# HHKBLite2BT.net
KiCad netlist of a schematic drawn in EAGLE
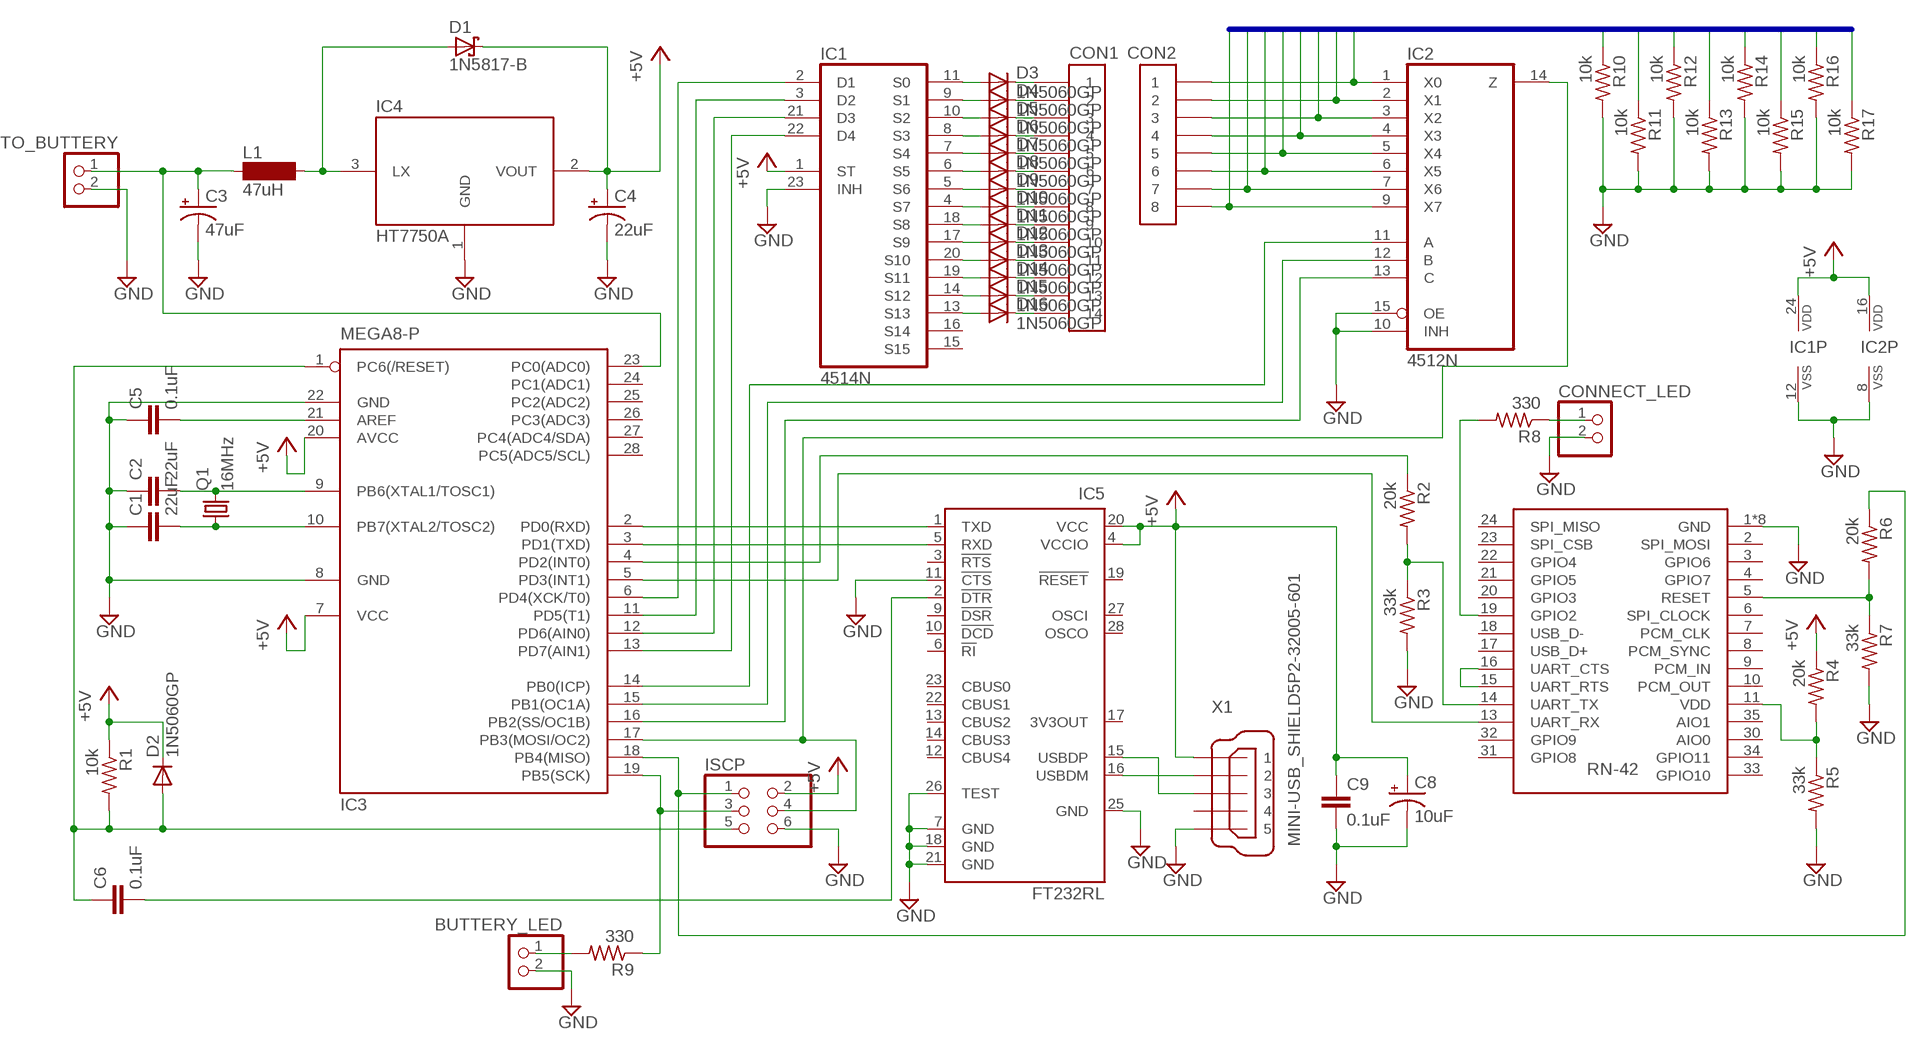
[diagram p0: schematic, sheet 1]

(export (version "E")
  (design (tool "Eeschema 10.0.6"))
  (components
    (comp (ref "BUTTERY_LED")
      (value "PINHD-1X2")
      (footprint "eagle-import:1X02")
      (libsource (lib "eagle-import") (part "PINHD-1X2"))
    )
    (comp (ref "C1")
      (value "22uF")
      (footprint "eagle-import:C5B2.5")
      (libsource (lib "eagle-import") (part "C5/2.5"))
    )
    (comp (ref "C2")
      (value "22uF")
      (footprint "eagle-import:C5B2.5")
      (libsource (lib "eagle-import") (part "C5/2.5"))
    )
    (comp (ref "C3")
      (value "47uF")
      (footprint "eagle-import:E5-10,5")
      (libsource (lib "eagle-import") (part "CPOL-USE5-10.5"))
    )
    (comp (ref "C4")
      (value "22uF")
      (footprint "eagle-import:E5-10,5")
      (libsource (lib "eagle-import") (part "CPOL-USE5-10.5"))
    )
    (comp (ref "C5")
      (value "0.1uF")
      (footprint "eagle-import:C5B2.5")
      (libsource (lib "eagle-import") (part "C5/2.5"))
    )
    (comp (ref "C6")
      (value "0.1uF")
      (footprint "eagle-import:C5B2.5")
      (libsource (lib "eagle-import") (part "C5/2.5"))
    )
    (comp (ref "C8")
      (value "10uF")
      (footprint "eagle-import:E5-10,5")
      (libsource (lib "eagle-import") (part "CPOL-USE5-10.5"))
    )
    (comp (ref "C9")
      (value "0.1uF")
      (footprint "eagle-import:C5B2.5")
      (libsource (lib "eagle-import") (part "C5/2.5"))
    )
    (comp (ref "CON1")
      (value "45045-1445")
      (footprint "eagle-import:52045-1445")
      (libsource (lib "eagle-import") (part "45045-1445"))
    )
    (comp (ref "CON2")
      (value "45045-0845")
      (footprint "eagle-import:52045-0845")
      (libsource (lib "eagle-import") (part "45045-0845"))
    )
    (comp (ref "CONNECT_LED")
      (value "PINHD-1X2")
      (footprint "eagle-import:1X02")
      (libsource (lib "eagle-import") (part "PINHD-1X2"))
    )
    (comp (ref "D1")
      (value "1N5817-B")
      (footprint "eagle-import:DO41-7.6")
      (libsource (lib "eagle-import") (part "1N5817-B"))
    )
    (comp (ref "D2")
      (value "1N5060GP")
      (footprint "eagle-import:DO15-12")
      (libsource (lib "eagle-import") (part "1N5060GP"))
    )
    (comp (ref "D3")
      (value "1N5060GP")
      (footprint "eagle-import:DO15-12")
      (libsource (lib "eagle-import") (part "1N5060GP"))
    )
    (comp (ref "D4")
      (value "1N5060GP")
      (footprint "eagle-import:DO15-12")
      (libsource (lib "eagle-import") (part "1N5060GP"))
    )
    (comp (ref "D5")
      (value "1N5060GP")
      (footprint "eagle-import:DO15-12")
      (libsource (lib "eagle-import") (part "1N5060GP"))
    )
    (comp (ref "D6")
      (value "1N5060GP")
      (footprint "eagle-import:DO15-12")
      (libsource (lib "eagle-import") (part "1N5060GP"))
    )
    (comp (ref "D7")
      (value "1N5060GP")
      (footprint "eagle-import:DO15-12")
      (libsource (lib "eagle-import") (part "1N5060GP"))
    )
    (comp (ref "D8")
      (value "1N5060GP")
      (footprint "eagle-import:DO15-12")
      (libsource (lib "eagle-import") (part "1N5060GP"))
    )
    (comp (ref "D9")
      (value "1N5060GP")
      (footprint "eagle-import:DO15-12")
      (libsource (lib "eagle-import") (part "1N5060GP"))
    )
    (comp (ref "D10")
      (value "1N5060GP")
      (footprint "eagle-import:DO15-12")
      (libsource (lib "eagle-import") (part "1N5060GP"))
    )
    (comp (ref "D11")
      (value "1N5060GP")
      (footprint "eagle-import:DO15-12")
      (libsource (lib "eagle-import") (part "1N5060GP"))
    )
    (comp (ref "D12")
      (value "1N5060GP")
      (footprint "eagle-import:DO15-12")
      (libsource (lib "eagle-import") (part "1N5060GP"))
    )
    (comp (ref "D13")
      (value "1N5060GP")
      (footprint "eagle-import:DO15-12")
      (libsource (lib "eagle-import") (part "1N5060GP"))
    )
    (comp (ref "D14")
      (value "1N5060GP")
      (footprint "eagle-import:DO15-12")
      (libsource (lib "eagle-import") (part "1N5060GP"))
    )
    (comp (ref "D15")
      (value "1N5060GP")
      (footprint "eagle-import:DO15-12")
      (libsource (lib "eagle-import") (part "1N5060GP"))
    )
    (comp (ref "D16")
      (value "1N5060GP")
      (footprint "eagle-import:DO15-12")
      (libsource (lib "eagle-import") (part "1N5060GP"))
    )
    (comp (ref "IC1")
      (value "4514N")
      (footprint "eagle-import:DIL24-6")
      (libsource (lib "eagle-import") (part "4514N"))
    )
    (comp (ref "IC2")
      (value "4512N")
      (footprint "eagle-import:DIL16")
      (libsource (lib "eagle-import") (part "4512N"))
    )
    (comp (ref "IC3")
      (value "MEGA8-P")
      (footprint "eagle-import:DIL28-3")
      (libsource (lib "eagle-import") (part "MEGA8-P"))
    )
    (comp (ref "IC4")
      (value "HT7750A")
      (footprint "eagle-import:TO-92")
      (libsource (lib "eagle-import") (part "HT7750A"))
    )
    (comp (ref "IC5")
      (value "FT232RL")
      (footprint "eagle-import:SSOP28")
      (libsource (lib "eagle-import") (part "FT232RL"))
    )
    (comp (ref "ISCP")
      (value "PINHD-2X3")
      (footprint "eagle-import:2X03")
      (libsource (lib "eagle-import") (part "PINHD-2X3"))
    )
    (comp (ref "L1")
      (value "47uH")
      (footprint "eagle-import:BS11")
      (libsource (lib "eagle-import") (part "BS11"))
    )
    (comp (ref "Q1")
      (value "16MHz")
      (footprint "eagle-import:HC49_S")
      (libsource (lib "eagle-import") (part "CRYSTALHC49S"))
    )
    (comp (ref "R1")
      (value "10k")
      (footprint "eagle-import:0207_7")
      (libsource (lib "eagle-import") (part "R-US_0207/7"))
    )
    (comp (ref "R2")
      (value "20k")
      (footprint "eagle-import:0207_7")
      (libsource (lib "eagle-import") (part "R-US_0207/7"))
    )
    (comp (ref "R3")
      (value "33k")
      (footprint "eagle-import:0207_7")
      (libsource (lib "eagle-import") (part "R-US_0207/7"))
    )
    (comp (ref "R4")
      (value "20k")
      (footprint "eagle-import:0207_7")
      (libsource (lib "eagle-import") (part "R-US_0207/7"))
    )
    (comp (ref "R5")
      (value "33k")
      (footprint "eagle-import:0207_7")
      (libsource (lib "eagle-import") (part "R-US_0207/7"))
    )
    (comp (ref "R6")
      (value "20k")
      (footprint "eagle-import:0207_7")
      (libsource (lib "eagle-import") (part "R-US_0207/7"))
    )
    (comp (ref "R7")
      (value "33k")
      (footprint "eagle-import:0207_7")
      (libsource (lib "eagle-import") (part "R-US_0207/7"))
    )
    (comp (ref "R8")
      (value "330")
      (footprint "eagle-import:0207_7")
      (libsource (lib "eagle-import") (part "R-US_0207/7"))
    )
    (comp (ref "R9")
      (value "330")
      (footprint "eagle-import:0207_7")
      (libsource (lib "eagle-import") (part "R-US_0207/7"))
    )
    (comp (ref "R10")
      (value "10k")
      (footprint "eagle-import:0207_7")
      (libsource (lib "eagle-import") (part "R-US_0207/7"))
    )
    (comp (ref "R11")
      (value "10k")
      (footprint "eagle-import:0207_7")
      (libsource (lib "eagle-import") (part "R-US_0207/7"))
    )
    (comp (ref "R12")
      (value "10k")
      (footprint "eagle-import:0207_7")
      (libsource (lib "eagle-import") (part "R-US_0207/7"))
    )
    (comp (ref "R13")
      (value "10k")
      (footprint "eagle-import:0207_7")
      (libsource (lib "eagle-import") (part "R-US_0207/7"))
    )
    (comp (ref "R14")
      (value "10k")
      (footprint "eagle-import:0207_7")
      (libsource (lib "eagle-import") (part "R-US_0207/7"))
    )
    (comp (ref "R15")
      (value "10k")
      (footprint "eagle-import:0207_7")
      (libsource (lib "eagle-import") (part "R-US_0207/7"))
    )
    (comp (ref "R16")
      (value "10k")
      (footprint "eagle-import:0207_7")
      (libsource (lib "eagle-import") (part "R-US_0207/7"))
    )
    (comp (ref "R17")
      (value "10k")
      (footprint "eagle-import:0207_7")
      (libsource (lib "eagle-import") (part "R-US_0207/7"))
    )
    (comp (ref "TO_BUTTERY")
      (value "PINHD-1X2")
      (footprint "eagle-import:1X02")
      (libsource (lib "eagle-import") (part "PINHD-1X2"))
    )
    (comp (ref "U$1")
      (value "RN-42")
      (footprint "eagle-import:RN-42")
      (libsource (lib "eagle-import") (part "RN-42"))
    )
    (comp (ref "X1")
      (value "MINI-USB_SHIELD5P2-32005-601")
      (footprint "eagle-import:32005-601")
      (libsource (lib "eagle-import") (part "MINI-USB_SHIELD5P2-32005-601"))
    )
  )
  (nets
    (net (code "1") (name "+5V") (class "Default")
      (node (ref "C4") (pin "+") (pinfunction "+_+") (pintype "passive"))
      (node (ref "C8") (pin "+") (pinfunction "+_+") (pintype "passive"))
      (node (ref "C9") (pin "1") (pinfunction "1_1") (pintype "passive"))
      (node (ref "D1") (pin "C") (pinfunction "C_C") (pintype "passive"))
      (node (ref "D2") (pin "C") (pinfunction "C_C") (pintype "passive"))
      (node (ref "IC1") (pin "1") (pinfunction "ST_1") (pintype "input"))
      (node (ref "IC1") (pin "24") (pinfunction "VDD_24") (pintype "power_in"))
      (node (ref "IC2") (pin "16") (pinfunction "VDD_16") (pintype "power_in"))
      (node (ref "IC3") (pin "20") (pinfunction "AVCC_20") (pintype "power_in"))
      (node (ref "IC3") (pin "7") (pinfunction "VCC_7") (pintype "power_in"))
      (node (ref "IC4") (pin "2") (pinfunction "VOUT_2") (pintype "output"))
      (node (ref "IC5") (pin "20") (pinfunction "VCC_20") (pintype "power_in"))
      (node (ref "IC5") (pin "4") (pinfunction "VCCIO_4") (pintype "power_in"))
      (node (ref "ISCP") (pin "2") (pinfunction "2_2") (pintype "passive"))
      (node (ref "R1") (pin "1") (pinfunction "1_1") (pintype "passive"))
      (node (ref "R4") (pin "1") (pinfunction "1_1") (pintype "passive"))
      (node (ref "X1") (pin "1") (pinfunction "1_1") (pintype "passive"))
    )
    (net (code "2") (name "/CON2BUS1") (class "Default")
      (node (ref "CON2") (pin "1") (pinfunction "1_1") (pintype "bidirectional"))
      (node (ref "IC2") (pin "1") (pinfunction "X0_1") (pintype "input"))
      (node (ref "R10") (pin "1") (pinfunction "1_1") (pintype "passive"))
    )
    (net (code "3") (name "/CON2BUS2") (class "Default")
      (node (ref "CON2") (pin "2") (pinfunction "2_2") (pintype "bidirectional"))
      (node (ref "IC2") (pin "2") (pinfunction "X1_2") (pintype "input"))
      (node (ref "R11") (pin "1") (pinfunction "1_1") (pintype "passive"))
    )
    (net (code "4") (name "/CON2BUS3") (class "Default")
      (node (ref "CON2") (pin "3") (pinfunction "3_3") (pintype "bidirectional"))
      (node (ref "IC2") (pin "3") (pinfunction "X2_3") (pintype "input"))
      (node (ref "R12") (pin "1") (pinfunction "1_1") (pintype "passive"))
    )
    (net (code "5") (name "/CON2BUS4") (class "Default")
      (node (ref "CON2") (pin "4") (pinfunction "4_4") (pintype "bidirectional"))
      (node (ref "IC2") (pin "4") (pinfunction "X3_4") (pintype "input"))
      (node (ref "R13") (pin "1") (pinfunction "1_1") (pintype "passive"))
    )
    (net (code "6") (name "/CON2BUS5") (class "Default")
      (node (ref "CON2") (pin "5") (pinfunction "5_5") (pintype "bidirectional"))
      (node (ref "IC2") (pin "5") (pinfunction "X4_5") (pintype "input"))
      (node (ref "R14") (pin "1") (pinfunction "1_1") (pintype "passive"))
    )
    (net (code "7") (name "/CON2BUS6") (class "Default")
      (node (ref "CON2") (pin "6") (pinfunction "6_6") (pintype "bidirectional"))
      (node (ref "IC2") (pin "6") (pinfunction "X5_6") (pintype "input"))
      (node (ref "R15") (pin "1") (pinfunction "1_1") (pintype "passive"))
    )
    (net (code "8") (name "/CON2BUS7") (class "Default")
      (node (ref "CON2") (pin "7") (pinfunction "7_7") (pintype "bidirectional"))
      (node (ref "IC2") (pin "7") (pinfunction "X6_7") (pintype "input"))
      (node (ref "R16") (pin "1") (pinfunction "1_1") (pintype "passive"))
    )
    (net (code "9") (name "/CON2BUS8") (class "Default")
      (node (ref "CON2") (pin "8") (pinfunction "8_8") (pintype "bidirectional"))
      (node (ref "IC2") (pin "9") (pinfunction "X7_9") (pintype "input"))
      (node (ref "R17") (pin "1") (pinfunction "1_1") (pintype "passive"))
    )
    (net (code "10") (name "GND") (class "Default")
      (node (ref "BUTTERY_LED") (pin "2") (pinfunction "2_2") (pintype "passive"))
      (node (ref "C1") (pin "1") (pinfunction "1_1") (pintype "passive"))
      (node (ref "C2") (pin "1") (pinfunction "1_1") (pintype "passive"))
      (node (ref "C3") (pin "-") (pinfunction "-_-") (pintype "passive"))
      (node (ref "C4") (pin "-") (pinfunction "-_-") (pintype "passive"))
      (node (ref "C5") (pin "1") (pinfunction "1_1") (pintype "passive"))
      (node (ref "C8") (pin "-") (pinfunction "-_-") (pintype "passive"))
      (node (ref "C9") (pin "2") (pinfunction "2_2") (pintype "passive"))
      (node (ref "CONNECT_LED") (pin "2") (pinfunction "2_2") (pintype "passive"))
      (node (ref "IC1") (pin "12") (pinfunction "VSS_12") (pintype "power_in"))
      (node (ref "IC1") (pin "23") (pinfunction "INH_23") (pintype "input"))
      (node (ref "IC2") (pin "10") (pinfunction "INH_10") (pintype "input"))
      (node (ref "IC2") (pin "15") (pinfunction "OE_15") (pintype "input"))
      (node (ref "IC2") (pin "8") (pinfunction "VSS_8") (pintype "power_in"))
      (node (ref "IC3") (pin "22") (pinfunction "GND_22") (pintype "power_in"))
      (node (ref "IC3") (pin "8") (pinfunction "GND_8") (pintype "power_in"))
      (node (ref "IC4") (pin "1") (pinfunction "GND_1") (pintype "power_in"))
      (node (ref "IC5") (pin "11") (pinfunction "~{CTS}_11") (pintype "input"))
      (node (ref "IC5") (pin "18") (pinfunction "GND_18") (pintype "power_in"))
      (node (ref "IC5") (pin "21") (pinfunction "GND_21") (pintype "power_in"))
      (node (ref "IC5") (pin "25") (pinfunction "GND_25") (pintype "power_in"))
      (node (ref "IC5") (pin "26") (pinfunction "TEST_26") (pintype "input"))
      (node (ref "IC5") (pin "7") (pinfunction "GND_7") (pintype "power_in"))
      (node (ref "ISCP") (pin "6") (pinfunction "6_6") (pintype "passive"))
      (node (ref "R10") (pin "2") (pinfunction "2_2") (pintype "passive"))
      (node (ref "R11") (pin "2") (pinfunction "2_2") (pintype "passive"))
      (node (ref "R12") (pin "2") (pinfunction "2_2") (pintype "passive"))
      (node (ref "R13") (pin "2") (pinfunction "2_2") (pintype "passive"))
      (node (ref "R14") (pin "2") (pinfunction "2_2") (pintype "passive"))
      (node (ref "R15") (pin "2") (pinfunction "2_2") (pintype "passive"))
      (node (ref "R16") (pin "2") (pinfunction "2_2") (pintype "passive"))
      (node (ref "R17") (pin "2") (pinfunction "2_2") (pintype "passive"))
      (node (ref "R3") (pin "2") (pinfunction "2_2") (pintype "passive"))
      (node (ref "R5") (pin "2") (pinfunction "2_2") (pintype "passive"))
      (node (ref "R7") (pin "2") (pinfunction "2_2") (pintype "passive"))
      (node (ref "TO_BUTTERY") (pin "2") (pinfunction "2_2") (pintype "passive"))
      (node (ref "U$1") (pin "1") (pinfunction "GND_1") (pintype "power_in"))
      (node (ref "U$1") (pin "12") (pinfunction "GND_12") (pintype "power_in"))
      (node (ref "U$1") (pin "28") (pinfunction "GND_28") (pintype "power_in"))
      (node (ref "U$1") (pin "29") (pinfunction "GND_29") (pintype "power_in"))
      (node (ref "U$1") (pin "GND1") (pinfunction "GND_GND1") (pintype "power_in"))
      (node (ref "U$1") (pin "GND2") (pinfunction "GND_GND2") (pintype "power_in"))
      (node (ref "U$1") (pin "GND3") (pinfunction "GND_GND3") (pintype "power_in"))
      (node (ref "U$1") (pin "GND4") (pinfunction "GND_GND4") (pintype "power_in"))
      (node (ref "X1") (pin "5") (pinfunction "5_5") (pintype "passive"))
    )
    (net (code "11") (name "Net-(BUTTERY_LED-Pad1)") (class "Default")
      (node (ref "BUTTERY_LED") (pin "1") (pinfunction "1_1") (pintype "passive"))
      (node (ref "R9") (pin "2") (pinfunction "2_2") (pintype "passive"))
    )
    (net (code "12") (name "Net-(CON1-Pad1)") (class "Default")
      (node (ref "CON1") (pin "1") (pinfunction "1_1") (pintype "bidirectional"))
      (node (ref "D3") (pin "C") (pinfunction "C_C") (pintype "passive"))
    )
    (net (code "13") (name "Net-(CON1-Pad2)") (class "Default")
      (node (ref "CON1") (pin "2") (pinfunction "2_2") (pintype "bidirectional"))
      (node (ref "D4") (pin "C") (pinfunction "C_C") (pintype "passive"))
    )
    (net (code "14") (name "Net-(CON1-Pad3)") (class "Default")
      (node (ref "CON1") (pin "3") (pinfunction "3_3") (pintype "bidirectional"))
      (node (ref "D5") (pin "C") (pinfunction "C_C") (pintype "passive"))
    )
    (net (code "15") (name "Net-(CON1-Pad4)") (class "Default")
      (node (ref "CON1") (pin "4") (pinfunction "4_4") (pintype "bidirectional"))
      (node (ref "D6") (pin "C") (pinfunction "C_C") (pintype "passive"))
    )
    (net (code "16") (name "Net-(CON1-Pad5)") (class "Default")
      (node (ref "CON1") (pin "5") (pinfunction "5_5") (pintype "bidirectional"))
      (node (ref "D7") (pin "C") (pinfunction "C_C") (pintype "passive"))
    )
    (net (code "17") (name "Net-(CON1-Pad6)") (class "Default")
      (node (ref "CON1") (pin "6") (pinfunction "6_6") (pintype "bidirectional"))
      (node (ref "D8") (pin "C") (pinfunction "C_C") (pintype "passive"))
    )
    (net (code "18") (name "Net-(CON1-Pad7)") (class "Default")
      (node (ref "CON1") (pin "7") (pinfunction "7_7") (pintype "bidirectional"))
      (node (ref "D9") (pin "C") (pinfunction "C_C") (pintype "passive"))
    )
    (net (code "19") (name "Net-(CON1-Pad8)") (class "Default")
      (node (ref "CON1") (pin "8") (pinfunction "8_8") (pintype "bidirectional"))
      (node (ref "D10") (pin "C") (pinfunction "C_C") (pintype "passive"))
    )
    (net (code "20") (name "Net-(CON1-Pad9)") (class "Default")
      (node (ref "CON1") (pin "9") (pinfunction "9_9") (pintype "bidirectional"))
      (node (ref "D11") (pin "C") (pinfunction "C_C") (pintype "passive"))
    )
    (net (code "21") (name "Net-(CON1-Pad10)") (class "Default")
      (node (ref "CON1") (pin "10") (pinfunction "10_10") (pintype "bidirectional"))
      (node (ref "D12") (pin "C") (pinfunction "C_C") (pintype "passive"))
    )
    (net (code "22") (name "Net-(CON1-Pad11)") (class "Default")
      (node (ref "CON1") (pin "11") (pinfunction "11_11") (pintype "bidirectional"))
      (node (ref "D13") (pin "C") (pinfunction "C_C") (pintype "passive"))
    )
    (net (code "23") (name "Net-(CON1-Pad12)") (class "Default")
      (node (ref "CON1") (pin "12") (pinfunction "12_12") (pintype "bidirectional"))
      (node (ref "D14") (pin "C") (pinfunction "C_C") (pintype "passive"))
    )
    (net (code "24") (name "Net-(CON1-Pad13)") (class "Default")
      (node (ref "CON1") (pin "13") (pinfunction "13_13") (pintype "bidirectional"))
      (node (ref "D15") (pin "C") (pinfunction "C_C") (pintype "passive"))
    )
    (net (code "25") (name "Net-(CON1-Pad14)") (class "Default")
      (node (ref "CON1") (pin "14") (pinfunction "14_14") (pintype "bidirectional"))
      (node (ref "D16") (pin "C") (pinfunction "C_C") (pintype "passive"))
    )
    (net (code "26") (name "Net-(CONNECT_LED-Pad1)") (class "Default")
      (node (ref "CONNECT_LED") (pin "1") (pinfunction "1_1") (pintype "passive"))
      (node (ref "R8") (pin "1") (pinfunction "1_1") (pintype "passive"))
    )
    (net (code "27") (name "Net-(IC1A-D1)") (class "Default")
      (node (ref "IC1") (pin "2") (pinfunction "D1_2") (pintype "input"))
      (node (ref "IC3") (pin "6") (pinfunction "PD4(XCK/T0)_6") (pintype "bidirectional"))
    )
    (net (code "28") (name "Net-(IC1A-D2)") (class "Default")
      (node (ref "IC1") (pin "3") (pinfunction "D2_3") (pintype "input"))
      (node (ref "IC3") (pin "11") (pinfunction "PD5(T1)_11") (pintype "bidirectional"))
    )
    (net (code "29") (name "Net-(IC1A-D3)") (class "Default")
      (node (ref "IC1") (pin "21") (pinfunction "D3_21") (pintype "input"))
      (node (ref "IC3") (pin "12") (pinfunction "PD6(AIN0)_12") (pintype "bidirectional"))
    )
    (net (code "30") (name "Net-(IC1A-D4)") (class "Default")
      (node (ref "IC1") (pin "22") (pinfunction "D4_22") (pintype "input"))
      (node (ref "IC3") (pin "13") (pinfunction "PD7(AIN1)_13") (pintype "bidirectional"))
    )
    (net (code "31") (name "Net-(IC1A-S0)") (class "Default")
      (node (ref "D3") (pin "A") (pinfunction "A_A") (pintype "passive"))
      (node (ref "IC1") (pin "11") (pinfunction "S0_11") (pintype "output"))
    )
    (net (code "32") (name "Net-(IC1A-S1)") (class "Default")
      (node (ref "D4") (pin "A") (pinfunction "A_A") (pintype "passive"))
      (node (ref "IC1") (pin "9") (pinfunction "S1_9") (pintype "output"))
    )
    (net (code "33") (name "Net-(IC1A-S2)") (class "Default")
      (node (ref "D5") (pin "A") (pinfunction "A_A") (pintype "passive"))
      (node (ref "IC1") (pin "10") (pinfunction "S2_10") (pintype "output"))
    )
    (net (code "34") (name "Net-(IC1A-S3)") (class "Default")
      (node (ref "D6") (pin "A") (pinfunction "A_A") (pintype "passive"))
      (node (ref "IC1") (pin "8") (pinfunction "S3_8") (pintype "output"))
    )
    (net (code "35") (name "Net-(IC1A-S4)") (class "Default")
      (node (ref "D7") (pin "A") (pinfunction "A_A") (pintype "passive"))
      (node (ref "IC1") (pin "7") (pinfunction "S4_7") (pintype "output"))
    )
    (net (code "36") (name "Net-(IC1A-S5)") (class "Default")
      (node (ref "D8") (pin "A") (pinfunction "A_A") (pintype "passive"))
      (node (ref "IC1") (pin "6") (pinfunction "S5_6") (pintype "output"))
    )
    (net (code "37") (name "Net-(IC1A-S6)") (class "Default")
      (node (ref "D9") (pin "A") (pinfunction "A_A") (pintype "passive"))
      (node (ref "IC1") (pin "5") (pinfunction "S6_5") (pintype "output"))
    )
    (net (code "38") (name "Net-(IC1A-S7)") (class "Default")
      (node (ref "D10") (pin "A") (pinfunction "A_A") (pintype "passive"))
      (node (ref "IC1") (pin "4") (pinfunction "S7_4") (pintype "output"))
    )
    (net (code "39") (name "Net-(IC1A-S8)") (class "Default")
      (node (ref "D11") (pin "A") (pinfunction "A_A") (pintype "passive"))
      (node (ref "IC1") (pin "18") (pinfunction "S8_18") (pintype "output"))
    )
    (net (code "40") (name "Net-(IC1A-S9)") (class "Default")
      (node (ref "D12") (pin "A") (pinfunction "A_A") (pintype "passive"))
      (node (ref "IC1") (pin "17") (pinfunction "S9_17") (pintype "output"))
    )
    (net (code "41") (name "Net-(IC1A-S10)") (class "Default")
      (node (ref "D13") (pin "A") (pinfunction "A_A") (pintype "passive"))
      (node (ref "IC1") (pin "20") (pinfunction "S10_20") (pintype "output"))
    )
    (net (code "42") (name "Net-(IC1A-S11)") (class "Default")
      (node (ref "D14") (pin "A") (pinfunction "A_A") (pintype "passive"))
      (node (ref "IC1") (pin "19") (pinfunction "S11_19") (pintype "output"))
    )
    (net (code "43") (name "Net-(IC1A-S12)") (class "Default")
      (node (ref "D15") (pin "A") (pinfunction "A_A") (pintype "passive"))
      (node (ref "IC1") (pin "14") (pinfunction "S12_14") (pintype "output"))
    )
    (net (code "44") (name "Net-(IC1A-S13)") (class "Default")
      (node (ref "D16") (pin "A") (pinfunction "A_A") (pintype "passive"))
      (node (ref "IC1") (pin "13") (pinfunction "S13_13") (pintype "output"))
    )
    (net (code "45") (name "Net-(IC2A-A)") (class "Default")
      (node (ref "IC2") (pin "11") (pinfunction "A_11") (pintype "input"))
      (node (ref "IC3") (pin "14") (pinfunction "PB0(ICP)_14") (pintype "bidirectional"))
    )
    (net (code "46") (name "Net-(IC2A-B)") (class "Default")
      (node (ref "IC2") (pin "12") (pinfunction "B_12") (pintype "input"))
      (node (ref "IC3") (pin "15") (pinfunction "PB1(OC1A)_15") (pintype "bidirectional"))
    )
    (net (code "47") (name "Net-(IC2A-C)") (class "Default")
      (node (ref "IC2") (pin "13") (pinfunction "C_13") (pintype "input"))
      (node (ref "IC3") (pin "16") (pinfunction "PB2(SS/OC1B)_16") (pintype "bidirectional"))
    )
    (net (code "48") (name "Net-(IC2A-Z)") (class "Default")
      (node (ref "IC2") (pin "14") (pinfunction "Z_14") (pintype "tri_state"))
      (node (ref "IC3") (pin "17") (pinfunction "PB3(MOSI/OC2)_17") (pintype "bidirectional"))
      (node (ref "ISCP") (pin "4") (pinfunction "4_4") (pintype "passive"))
    )
    (net (code "49") (name "Net-(IC3-AREF)") (class "Default")
      (node (ref "C5") (pin "2") (pinfunction "2_2") (pintype "passive"))
      (node (ref "IC3") (pin "21") (pinfunction "AREF_21") (pintype "passive"))
    )
    (net (code "50") (name "Net-(IC3-PB4(MISO))") (class "Default")
      (node (ref "IC3") (pin "18") (pinfunction "PB4(MISO)_18") (pintype "bidirectional"))
      (node (ref "ISCP") (pin "1") (pinfunction "1_1") (pintype "passive"))
      (node (ref "R6") (pin "1") (pinfunction "1_1") (pintype "passive"))
    )
    (net (code "51") (name "Net-(IC3-PB5(SCK))") (class "Default")
      (node (ref "IC3") (pin "19") (pinfunction "PB5(SCK)_19") (pintype "bidirectional"))
      (node (ref "ISCP") (pin "3") (pinfunction "3_3") (pintype "passive"))
      (node (ref "R9") (pin "1") (pinfunction "1_1") (pintype "passive"))
    )
    (net (code "52") (name "Net-(IC3-PB6(XTAL1{slash}TOSC1))") (class "Default")
      (node (ref "C2") (pin "2") (pinfunction "2_2") (pintype "passive"))
      (node (ref "IC3") (pin "9") (pinfunction "PB6(XTAL1/TOSC1)_9") (pintype "bidirectional"))
      (node (ref "Q1") (pin "2") (pinfunction "2_2") (pintype "passive"))
    )
    (net (code "53") (name "Net-(IC3-PB7(XTAL2{slash}TOSC2))") (class "Default")
      (node (ref "C1") (pin "2") (pinfunction "2_2") (pintype "passive"))
      (node (ref "IC3") (pin "10") (pinfunction "PB7(XTAL2/TOSC2)_10") (pintype "bidirectional"))
      (node (ref "Q1") (pin "1") (pinfunction "1_1") (pintype "passive"))
    )
    (net (code "54") (name "Net-(IC3-PC0(ADC0))") (class "Default")
      (node (ref "C3") (pin "+") (pinfunction "+_+") (pintype "passive"))
      (node (ref "IC3") (pin "23") (pinfunction "PC0(ADC0)_23") (pintype "bidirectional"))
      (node (ref "L1") (pin "1") (pinfunction "1_1") (pintype "passive"))
      (node (ref "TO_BUTTERY") (pin "1") (pinfunction "1_1") (pintype "passive"))
    )
    (net (code "55") (name "Net-(IC3-PC6({slash}RESET))") (class "Default")
      (node (ref "C6") (pin "1") (pinfunction "1_1") (pintype "passive"))
      (node (ref "D2") (pin "A") (pinfunction "A_A") (pintype "passive"))
      (node (ref "IC3") (pin "1") (pinfunction "PC6(/RESET)_1") (pintype "bidirectional"))
      (node (ref "ISCP") (pin "5") (pinfunction "5_5") (pintype "passive"))
      (node (ref "R1") (pin "2") (pinfunction "2_2") (pintype "passive"))
    )
    (net (code "56") (name "Net-(IC3-PD0(RXD))") (class "Default")
      (node (ref "IC3") (pin "2") (pinfunction "PD0(RXD)_2") (pintype "bidirectional"))
      (node (ref "IC5") (pin "1") (pinfunction "TXD_1") (pintype "output"))
    )
    (net (code "57") (name "Net-(IC3-PD1(TXD))") (class "Default")
      (node (ref "IC3") (pin "3") (pinfunction "PD1(TXD)_3") (pintype "bidirectional"))
      (node (ref "IC5") (pin "5") (pinfunction "RXD_5") (pintype "input"))
    )
    (net (code "58") (name "Net-(IC3-PD2(INT0))") (class "Default")
      (node (ref "IC3") (pin "4") (pinfunction "PD2(INT0)_4") (pintype "bidirectional"))
      (node (ref "R2") (pin "1") (pinfunction "1_1") (pintype "passive"))
    )
    (net (code "59") (name "Net-(IC3-PD3(INT1))") (class "Default")
      (node (ref "IC3") (pin "5") (pinfunction "PD3(INT1)_5") (pintype "bidirectional"))
      (node (ref "U$1") (pin "13") (pinfunction "UART_RX_13") (pintype "bidirectional"))
    )
    (net (code "60") (name "Net-(IC4-LX)") (class "Default")
      (node (ref "D1") (pin "A") (pinfunction "A_A") (pintype "passive"))
      (node (ref "IC4") (pin "3") (pinfunction "LX_3") (pintype "input"))
      (node (ref "L1") (pin "2") (pinfunction "2_2") (pintype "passive"))
    )
    (net (code "61") (name "Net-(IC5-USBDM)") (class "Default")
      (node (ref "IC5") (pin "16") (pinfunction "USBDM_16") (pintype "bidirectional"))
      (node (ref "X1") (pin "2") (pinfunction "2_2") (pintype "passive"))
    )
    (net (code "62") (name "Net-(IC5-USBDP)") (class "Default")
      (node (ref "IC5") (pin "15") (pinfunction "USBDP_15") (pintype "bidirectional"))
      (node (ref "X1") (pin "3") (pinfunction "3_3") (pintype "passive"))
    )
    (net (code "63") (name "Net-(IC5-~{DTR})") (class "Default")
      (node (ref "C6") (pin "2") (pinfunction "2_2") (pintype "passive"))
      (node (ref "IC5") (pin "2") (pinfunction "~{DTR}_2") (pintype "output"))
    )
    (net (code "64") (name "Net-(U$1-GPIO2)") (class "Default")
      (node (ref "R8") (pin "2") (pinfunction "2_2") (pintype "passive"))
      (node (ref "U$1") (pin "19") (pinfunction "GPIO2_19") (pintype "bidirectional"))
    )
    (net (code "65") (name "Net-(U$1-RESET)") (class "Default")
      (node (ref "R6") (pin "2") (pinfunction "2_2") (pintype "passive"))
      (node (ref "R7") (pin "1") (pinfunction "1_1") (pintype "passive"))
      (node (ref "U$1") (pin "5") (pinfunction "RESET_5") (pintype "bidirectional"))
    )
    (net (code "66") (name "Net-(U$1-UART_CTS)") (class "Default")
      (node (ref "U$1") (pin "15") (pinfunction "UART_RTS_15") (pintype "bidirectional"))
      (node (ref "U$1") (pin "16") (pinfunction "UART_CTS_16") (pintype "bidirectional"))
    )
    (net (code "67") (name "Net-(U$1-UART_TX)") (class "Default")
      (node (ref "R2") (pin "2") (pinfunction "2_2") (pintype "passive"))
      (node (ref "R3") (pin "1") (pinfunction "1_1") (pintype "passive"))
      (node (ref "U$1") (pin "14") (pinfunction "UART_TX_14") (pintype "bidirectional"))
    )
    (net (code "68") (name "Net-(U$1-VDD)") (class "Default")
      (node (ref "R4") (pin "2") (pinfunction "2_2") (pintype "passive"))
      (node (ref "R5") (pin "1") (pinfunction "1_1") (pintype "passive"))
      (node (ref "U$1") (pin "11") (pinfunction "VDD_11") (pintype "power_in"))
    )
    (net (code "69") (name "unconnected-(IC1A-S14-Pad16)") (class "Default")
      (node (ref "IC1") (pin "16") (pinfunction "S14_16") (pintype "output"))
    )
    (net (code "70") (name "unconnected-(IC1A-S15-Pad15)") (class "Default")
      (node (ref "IC1") (pin "15") (pinfunction "S15_15") (pintype "output"))
    )
    (net (code "71") (name "unconnected-(IC3-PC1(ADC1)-Pad24)") (class "Default")
      (node (ref "IC3") (pin "24") (pinfunction "PC1(ADC1)_24") (pintype "bidirectional"))
    )
    (net (code "72") (name "unconnected-(IC3-PC2(ADC2)-Pad25)") (class "Default")
      (node (ref "IC3") (pin "25") (pinfunction "PC2(ADC2)_25") (pintype "bidirectional"))
    )
    (net (code "73") (name "unconnected-(IC3-PC3(ADC3)-Pad26)") (class "Default")
      (node (ref "IC3") (pin "26") (pinfunction "PC3(ADC3)_26") (pintype "bidirectional"))
    )
    (net (code "74") (name "unconnected-(IC3-PC4(ADC4{slash}SDA)-Pad27)") (class "Default")
      (node (ref "IC3") (pin "27") (pinfunction "PC4(ADC4/SDA)_27") (pintype "bidirectional"))
    )
    (net (code "75") (name "unconnected-(IC3-PC5(ADC5{slash}SCL)-Pad28)") (class "Default")
      (node (ref "IC3") (pin "28") (pinfunction "PC5(ADC5/SCL)_28") (pintype "bidirectional"))
    )
    (net (code "76") (name "unconnected-(IC5-3V3OUT-Pad17)") (class "Default")
      (node (ref "IC5") (pin "17") (pinfunction "3V3OUT_17") (pintype "output"))
    )
    (net (code "77") (name "unconnected-(IC5-CBUS0-Pad23)") (class "Default")
      (node (ref "IC5") (pin "23") (pinfunction "CBUS0_23") (pintype "bidirectional"))
    )
    (net (code "78") (name "unconnected-(IC5-CBUS1-Pad22)") (class "Default")
      (node (ref "IC5") (pin "22") (pinfunction "CBUS1_22") (pintype "bidirectional"))
    )
    (net (code "79") (name "unconnected-(IC5-CBUS2-Pad13)") (class "Default")
      (node (ref "IC5") (pin "13") (pinfunction "CBUS2_13") (pintype "bidirectional"))
    )
    (net (code "80") (name "unconnected-(IC5-CBUS3-Pad14)") (class "Default")
      (node (ref "IC5") (pin "14") (pinfunction "CBUS3_14") (pintype "bidirectional"))
    )
    (net (code "81") (name "unconnected-(IC5-CBUS4-Pad12)") (class "Default")
      (node (ref "IC5") (pin "12") (pinfunction "CBUS4_12") (pintype "bidirectional"))
    )
    (net (code "82") (name "unconnected-(IC5-OSCI-Pad27)") (class "Default")
      (node (ref "IC5") (pin "27") (pinfunction "OSCI_27") (pintype "input"))
    )
    (net (code "83") (name "unconnected-(IC5-OSCO-Pad28)") (class "Default")
      (node (ref "IC5") (pin "28") (pinfunction "OSCO_28") (pintype "output"))
    )
    (net (code "84") (name "unconnected-(IC5-~{DCD}-Pad10)") (class "Default")
      (node (ref "IC5") (pin "10") (pinfunction "~{DCD}_10") (pintype "input"))
    )
    (net (code "85") (name "unconnected-(IC5-~{DSR}-Pad9)") (class "Default")
      (node (ref "IC5") (pin "9") (pinfunction "~{DSR}_9") (pintype "input"))
    )
    (net (code "86") (name "unconnected-(IC5-~{RESET}-Pad19)") (class "Default")
      (node (ref "IC5") (pin "19") (pinfunction "~{RESET}_19") (pintype "input"))
    )
    (net (code "87") (name "unconnected-(IC5-~{RI}-Pad6)") (class "Default")
      (node (ref "IC5") (pin "6") (pinfunction "~{RI}_6") (pintype "input"))
    )
    (net (code "88") (name "unconnected-(IC5-~{RTS}-Pad3)") (class "Default")
      (node (ref "IC5") (pin "3") (pinfunction "~{RTS}_3") (pintype "output"))
    )
    (net (code "89") (name "unconnected-(U$1-AIO0-Pad30)") (class "Default")
      (node (ref "U$1") (pin "30") (pinfunction "AIO0_30") (pintype "bidirectional"))
    )
    (net (code "90") (name "unconnected-(U$1-AIO1-Pad35)") (class "Default")
      (node (ref "U$1") (pin "35") (pinfunction "AIO1_35") (pintype "bidirectional"))
    )
    (net (code "91") (name "unconnected-(U$1-GPIO3-Pad20)") (class "Default")
      (node (ref "U$1") (pin "20") (pinfunction "GPIO3_20") (pintype "bidirectional"))
    )
    (net (code "92") (name "unconnected-(U$1-GPIO4-Pad22)") (class "Default")
      (node (ref "U$1") (pin "22") (pinfunction "GPIO4_22") (pintype "bidirectional"))
    )
    (net (code "93") (name "unconnected-(U$1-GPIO5-Pad21)") (class "Default")
      (node (ref "U$1") (pin "21") (pinfunction "GPIO5_21") (pintype "bidirectional"))
    )
    (net (code "94") (name "unconnected-(U$1-GPIO6-Pad3)") (class "Default")
      (node (ref "U$1") (pin "3") (pinfunction "GPIO6_3") (pintype "bidirectional"))
    )
    (net (code "95") (name "unconnected-(U$1-GPIO7-Pad4)") (class "Default")
      (node (ref "U$1") (pin "4") (pinfunction "GPIO7_4") (pintype "bidirectional"))
    )
    (net (code "96") (name "unconnected-(U$1-GPIO8-Pad31)") (class "Default")
      (node (ref "U$1") (pin "31") (pinfunction "GPIO8_31") (pintype "bidirectional"))
    )
    (net (code "97") (name "unconnected-(U$1-GPIO9-Pad32)") (class "Default")
      (node (ref "U$1") (pin "32") (pinfunction "GPIO9_32") (pintype "bidirectional"))
    )
    (net (code "98") (name "unconnected-(U$1-GPIO10-Pad33)") (class "Default")
      (node (ref "U$1") (pin "33") (pinfunction "GPIO10_33") (pintype "bidirectional"))
    )
    (net (code "99") (name "unconnected-(U$1-GPIO11-Pad34)") (class "Default")
      (node (ref "U$1") (pin "34") (pinfunction "GPIO11_34") (pintype "bidirectional"))
    )
    (net (code "100") (name "unconnected-(U$1-PCM_CLK-Pad7)") (class "Default")
      (node (ref "U$1") (pin "7") (pinfunction "PCM_CLK_7") (pintype "bidirectional"))
    )
    (net (code "101") (name "unconnected-(U$1-PCM_IN-Pad9)") (class "Default")
      (node (ref "U$1") (pin "9") (pinfunction "PCM_IN_9") (pintype "bidirectional"))
    )
    (net (code "102") (name "unconnected-(U$1-PCM_OUT-Pad10)") (class "Default")
      (node (ref "U$1") (pin "10") (pinfunction "PCM_OUT_10") (pintype "bidirectional"))
    )
    (net (code "103") (name "unconnected-(U$1-PCM_SYNC-Pad8)") (class "Default")
      (node (ref "U$1") (pin "8") (pinfunction "PCM_SYNC_8") (pintype "bidirectional"))
    )
    (net (code "104") (name "unconnected-(U$1-SPI_CLOCK-Pad6)") (class "Default")
      (node (ref "U$1") (pin "6") (pinfunction "SPI_CLOCK_6") (pintype "bidirectional"))
    )
    (net (code "105") (name "unconnected-(U$1-SPI_CSB-Pad23)") (class "Default")
      (node (ref "U$1") (pin "23") (pinfunction "SPI_CSB_23") (pintype "bidirectional"))
    )
    (net (code "106") (name "unconnected-(U$1-SPI_MISO-Pad24)") (class "Default")
      (node (ref "U$1") (pin "24") (pinfunction "SPI_MISO_24") (pintype "bidirectional"))
    )
    (net (code "107") (name "unconnected-(U$1-SPI_MOSI-Pad2)") (class "Default")
      (node (ref "U$1") (pin "2") (pinfunction "SPI_MOSI_2") (pintype "bidirectional"))
    )
    (net (code "108") (name "unconnected-(U$1-USB_D+-Pad17)") (class "Default")
      (node (ref "U$1") (pin "17") (pinfunction "USB_D+_17") (pintype "bidirectional"))
    )
    (net (code "109") (name "unconnected-(U$1-USB_D--Pad18)") (class "Default")
      (node (ref "U$1") (pin "18") (pinfunction "USB_D-_18") (pintype "bidirectional"))
    )
    (net (code "110") (name "unconnected-(X1-Pad4)") (class "Default")
      (node (ref "X1") (pin "4") (pinfunction "4_4") (pintype "passive"))
    )
  )
)
